# MCU_board_v1_1.net
KiCad netlist of a schematic drawn in EAGLE
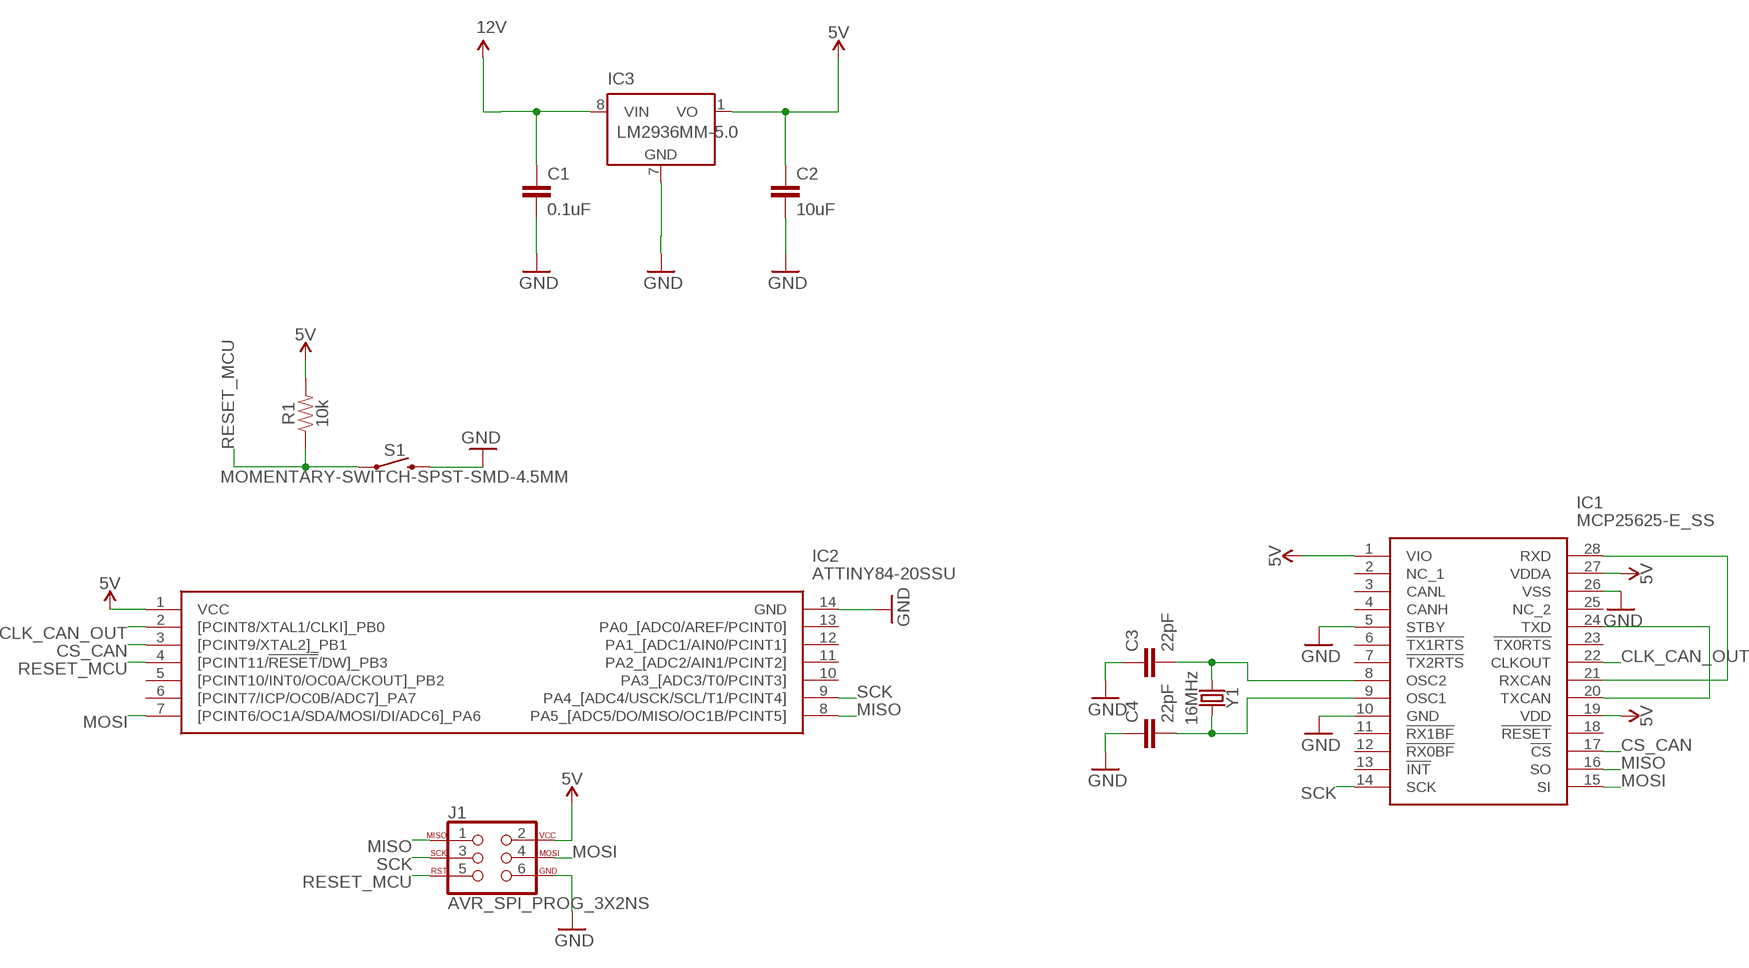
[diagram p0: schematic, sheet 1]

(export (version "E")
  (design (tool "Eeschema 10.0.6"))
  (components
    (comp (ref "C1")
      (value "0.1uF")
      (footprint "eagle-import:0402")
      (libsource (lib "eagle-import") (part "0.1UF-0402-16V-10%"))
    )
    (comp (ref "C2")
      (value "10uF")
      (footprint "eagle-import:0603")
      (libsource (lib "eagle-import") (part "10UF-0603-6.3V-20%"))
    )
    (comp (ref "C3")
      (value "22pF")
      (footprint "eagle-import:0603")
      (libsource (lib "eagle-import") (part "22PF-0603-50V-5%"))
    )
    (comp (ref "C4")
      (value "22pF")
      (footprint "eagle-import:0603")
      (libsource (lib "eagle-import") (part "22PF-0603-50V-5%"))
    )
    (comp (ref "IC1")
      (value "MCP25625-E_SS")
      (footprint "eagle-import:SOP65P780X200-28N")
      (fields (field (name "ARROW_PART_NUMBER") "MCP25625-E/SS") (field (name "RS_PART_NUMBER") "1651935"))
      (libsource (lib "eagle-import") (part "MCP25625-E_SS"))
    )
    (comp (ref "IC2")
      (value "ATTINY84-20SSU")
      (footprint "eagle-import:SOIC127P600X175-14N")
      (fields (field (name "RS_PART_NUMBER") "9214633"))
      (libsource (lib "eagle-import") (part "ATTINY84-20SSU"))
    )
    (comp (ref "IC3")
      (value "LM2936MM-5.0")
      (footprint "eagle-import:MINI-SO8")
      (fields (field (name "MF") "NATIONAL SEMICONDUCTOR") (field (name "MPN") "LM2936MM-5.0/NOPB"))
      (libsource (lib "eagle-import") (part "LM2936?MM-5.0"))
    )
    (comp (ref "J1")
      (value "AVR_SPI_PROG_3X2NS")
      (footprint "eagle-import:2X3-NS")
      (libsource (lib "eagle-import") (part "AVR_SPI_PROG_3X2NS"))
    )
    (comp (ref "R1")
      (value "10k")
      (footprint "eagle-import:0603")
      (libsource (lib "eagle-import") (part "10KOHM-0603-1/10W-1%"))
    )
    (comp (ref "S1")
      (value "MOMENTARY-SWITCH-SPST-SMD-4.5MM")
      (footprint "eagle-import:TACTILE_SWITCH_SMD_4.5MM")
      (libsource (lib "eagle-import") (part "MOMENTARY-SWITCH-SPST-SMD-4.5MM"))
    )
    (comp (ref "Y1")
      (value "16MHz")
      (footprint "eagle-import:CRYSTAL-SMD-5X3.2-4PAD")
      (libsource (lib "eagle-import") (part "CRYSTAL-16MHZSMD-5X3.2"))
    )
  )
  (nets
    (net (code "1") (name "/CLK_CAN_OUT") (class "Default")
      (node (ref "IC1") (pin "22") (pinfunction "CLKOUT_22") (pintype "bidirectional"))
      (node (ref "IC2") (pin "2") (pinfunction "[PCINT8/XTAL1/CLKI]_PB0_2") (pintype "input"))
    )
    (net (code "2") (name "/CS_CAN") (class "Default")
      (node (ref "IC1") (pin "17") (pinfunction "~{CS}_17") (pintype "bidirectional"))
      (node (ref "IC2") (pin "3") (pinfunction "[PCINT9/XTAL2]_PB1_3") (pintype "input"))
    )
    (net (code "3") (name "/MISO") (class "Default")
      (node (ref "IC1") (pin "16") (pinfunction "SO_16") (pintype "bidirectional"))
      (node (ref "IC2") (pin "8") (pinfunction "PA5_[ADC5/DO/MISO/OC1B/PCINT5]_8") (pintype "input"))
      (node (ref "J1") (pin "1") (pinfunction "1_1") (pintype "passive"))
    )
    (net (code "4") (name "/MOSI") (class "Default")
      (node (ref "IC1") (pin "15") (pinfunction "SI_15") (pintype "bidirectional"))
      (node (ref "IC2") (pin "7") (pinfunction "[PCINT6/OC1A/SDA/MOSI/DI/ADC6]_PA6_7") (pintype "input"))
      (node (ref "J1") (pin "4") (pinfunction "4_4") (pintype "passive"))
    )
    (net (code "5") (name "/RESET_MCU") (class "Default")
      (node (ref "IC2") (pin "4") (pinfunction "[PCINT11/~{RESET}/DW]_PB3_4") (pintype "input"))
      (node (ref "J1") (pin "5") (pinfunction "5_5") (pintype "passive"))
      (node (ref "R1") (pin "1") (pinfunction "1_1") (pintype "passive"))
      (node (ref "S1") (pin "2") (pinfunction "1_2") (pintype "passive"))
      (node (ref "S1") (pin "3") (pinfunction "1_3") (pintype "passive"))
    )
    (net (code "6") (name "/SCK") (class "Default")
      (node (ref "IC1") (pin "14") (pinfunction "SCK_14") (pintype "bidirectional"))
      (node (ref "IC2") (pin "9") (pinfunction "PA4_[ADC4/USCK/SCL/T1/PCINT4]_9") (pintype "input"))
      (node (ref "J1") (pin "3") (pinfunction "3_3") (pintype "passive"))
    )
    (net (code "7") (name "5V") (class "Default")
      (node (ref "C2") (pin "1") (pinfunction "1_1") (pintype "passive"))
      (node (ref "IC1") (pin "1") (pinfunction "VIO_1") (pintype "bidirectional"))
      (node (ref "IC1") (pin "19") (pinfunction "VDD_19") (pintype "bidirectional"))
      (node (ref "IC1") (pin "27") (pinfunction "VDDA_27") (pintype "bidirectional"))
      (node (ref "IC2") (pin "1") (pinfunction "VCC_1") (pintype "power_in"))
      (node (ref "IC3") (pin "1") (pinfunction "VO_1") (pintype "passive"))
      (node (ref "J1") (pin "2") (pinfunction "2_2") (pintype "passive"))
      (node (ref "R1") (pin "2") (pinfunction "2_2") (pintype "passive"))
    )
    (net (code "8") (name "12V") (class "Default")
      (node (ref "C1") (pin "1") (pinfunction "1_1") (pintype "passive"))
      (node (ref "IC3") (pin "8") (pinfunction "VIN_8") (pintype "input"))
    )
    (net (code "9") (name "GND") (class "Default")
      (node (ref "C1") (pin "2") (pinfunction "2_2") (pintype "passive"))
      (node (ref "C2") (pin "2") (pinfunction "2_2") (pintype "passive"))
      (node (ref "C3") (pin "1") (pinfunction "1_1") (pintype "passive"))
      (node (ref "C4") (pin "1") (pinfunction "1_1") (pintype "passive"))
      (node (ref "IC1") (pin "10") (pinfunction "GND_10") (pintype "bidirectional"))
      (node (ref "IC1") (pin "26") (pinfunction "VSS_26") (pintype "bidirectional"))
      (node (ref "IC1") (pin "5") (pinfunction "STBY_5") (pintype "bidirectional"))
      (node (ref "IC2") (pin "14") (pinfunction "GND_14") (pintype "power_in"))
      (node (ref "IC3") (pin "7") (pinfunction "GND_7") (pintype "passive"))
      (node (ref "J1") (pin "6") (pinfunction "6_6") (pintype "passive"))
      (node (ref "S1") (pin "1") (pinfunction "2_1") (pintype "passive"))
      (node (ref "S1") (pin "4") (pinfunction "2_4") (pintype "passive"))
    )
    (net (code "10") (name "Net-(IC1-OSC1)") (class "Default")
      (node (ref "C4") (pin "2") (pinfunction "2_2") (pintype "passive"))
      (node (ref "IC1") (pin "9") (pinfunction "OSC1_9") (pintype "bidirectional"))
      (node (ref "Y1") (pin "3") (pinfunction "2_3") (pintype "passive"))
    )
    (net (code "11") (name "Net-(IC1-OSC2)") (class "Default")
      (node (ref "C3") (pin "2") (pinfunction "2_2") (pintype "passive"))
      (node (ref "IC1") (pin "8") (pinfunction "OSC2_8") (pintype "bidirectional"))
      (node (ref "Y1") (pin "1") (pinfunction "1_1") (pintype "passive"))
    )
    (net (code "12") (name "Net-(IC1-RXCAN)") (class "Default")
      (node (ref "IC1") (pin "21") (pinfunction "RXCAN_21") (pintype "bidirectional"))
      (node (ref "IC1") (pin "28") (pinfunction "RXD_28") (pintype "bidirectional"))
    )
    (net (code "13") (name "Net-(IC1-TXCAN)") (class "Default")
      (node (ref "IC1") (pin "20") (pinfunction "TXCAN_20") (pintype "bidirectional"))
      (node (ref "IC1") (pin "24") (pinfunction "TXD_24") (pintype "bidirectional"))
    )
    (net (code "14") (name "unconnected-(IC1-CANH-Pad4)") (class "Default")
      (node (ref "IC1") (pin "4") (pinfunction "CANH_4") (pintype "bidirectional"))
    )
    (net (code "15") (name "unconnected-(IC1-CANL-Pad3)") (class "Default")
      (node (ref "IC1") (pin "3") (pinfunction "CANL_3") (pintype "bidirectional"))
    )
    (net (code "16") (name "unconnected-(IC1-NC_1-Pad2)") (class "Default")
      (node (ref "IC1") (pin "2") (pinfunction "NC_1_2") (pintype "bidirectional"))
    )
    (net (code "17") (name "unconnected-(IC1-NC_2-Pad25)") (class "Default")
      (node (ref "IC1") (pin "25") (pinfunction "NC_2_25") (pintype "bidirectional"))
    )
    (net (code "18") (name "unconnected-(IC1-~{INT}-Pad13)") (class "Default")
      (node (ref "IC1") (pin "13") (pinfunction "~{INT}_13") (pintype "bidirectional"))
    )
    (net (code "19") (name "unconnected-(IC1-~{RESET}-Pad18)") (class "Default")
      (node (ref "IC1") (pin "18") (pinfunction "~{RESET}_18") (pintype "bidirectional"))
    )
    (net (code "20") (name "unconnected-(IC1-~{RX0BF}-Pad12)") (class "Default")
      (node (ref "IC1") (pin "12") (pinfunction "~{RX0BF}_12") (pintype "bidirectional"))
    )
    (net (code "21") (name "unconnected-(IC1-~{RX1BF}-Pad11)") (class "Default")
      (node (ref "IC1") (pin "11") (pinfunction "~{RX1BF}_11") (pintype "bidirectional"))
    )
    (net (code "22") (name "unconnected-(IC1-~{TX0RTS}-Pad23)") (class "Default")
      (node (ref "IC1") (pin "23") (pinfunction "~{TX0RTS}_23") (pintype "bidirectional"))
    )
    (net (code "23") (name "unconnected-(IC1-~{TX1RTS}-Pad6)") (class "Default")
      (node (ref "IC1") (pin "6") (pinfunction "~{TX1RTS}_6") (pintype "bidirectional"))
    )
    (net (code "24") (name "unconnected-(IC1-~{TX2RTS}-Pad7)") (class "Default")
      (node (ref "IC1") (pin "7") (pinfunction "~{TX2RTS}_7") (pintype "bidirectional"))
    )
    (net (code "25") (name "unconnected-(IC2-PA0_[ADC0{slash}AREF{slash}PCINT0]-Pad13)") (class "Default")
      (node (ref "IC2") (pin "13") (pinfunction "PA0_[ADC0/AREF/PCINT0]_13") (pintype "input"))
    )
    (net (code "26") (name "unconnected-(IC2-PA1_[ADC1{slash}AIN0{slash}PCINT1]-Pad12)") (class "Default")
      (node (ref "IC2") (pin "12") (pinfunction "PA1_[ADC1/AIN0/PCINT1]_12") (pintype "input"))
    )
    (net (code "27") (name "unconnected-(IC2-PA2_[ADC2{slash}AIN1{slash}PCINT2]-Pad11)") (class "Default")
      (node (ref "IC2") (pin "11") (pinfunction "PA2_[ADC2/AIN1/PCINT2]_11") (pintype "input"))
    )
    (net (code "28") (name "unconnected-(IC2-PA3_[ADC3{slash}T0{slash}PCINT3]-Pad10)") (class "Default")
      (node (ref "IC2") (pin "10") (pinfunction "PA3_[ADC3/T0/PCINT3]_10") (pintype "input"))
    )
    (net (code "29") (name "unconnected-(IC2-[PCINT7{slash}ICP{slash}OC0B{slash}ADC7]_PA7-Pad6)") (class "Default")
      (node (ref "IC2") (pin "6") (pinfunction "[PCINT7/ICP/OC0B/ADC7]_PA7_6") (pintype "input"))
    )
    (net (code "30") (name "unconnected-(IC2-[PCINT10{slash}INT0{slash}OC0A{slash}CKOUT]_PB2-Pad5)") (class "Default")
      (node (ref "IC2") (pin "5") (pinfunction "[PCINT10/INT0/OC0A/CKOUT]_PB2_5") (pintype "output"))
    )
  )
)
